# P6.net
KiCad netlist of a schematic drawn in Altium Designer
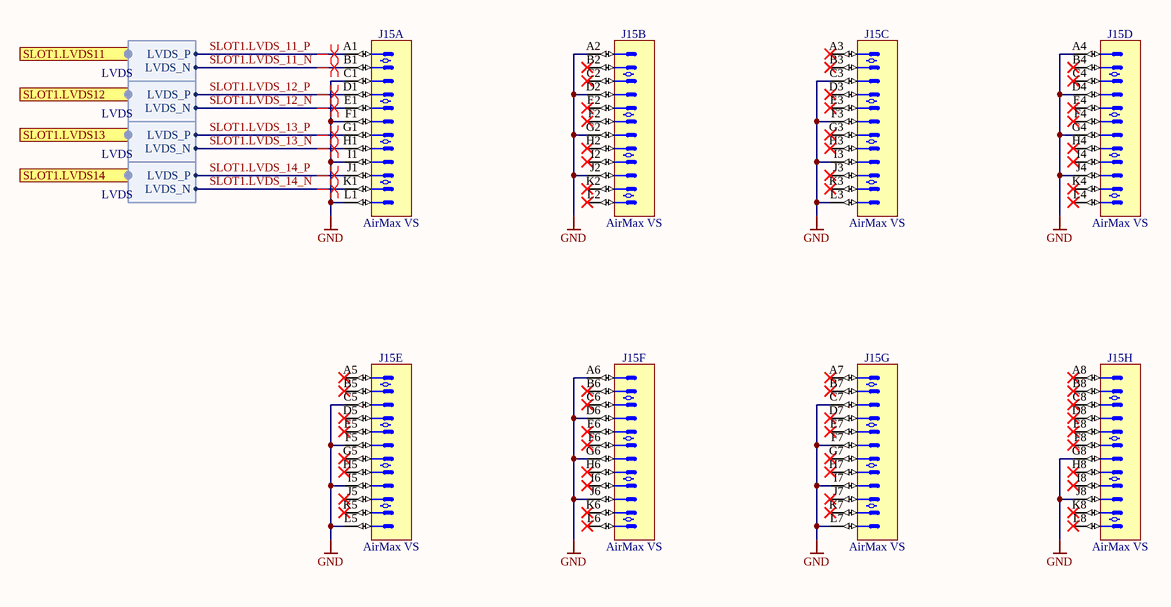
[diagram p0: P6.SchDoc]

(export (version "E")
  (design (tool "Eeschema 10.0.6"))
  (components
    (comp (ref "J15")
      (value "AirMax VS")
      (footprint "AMPHENOL_10052838-101LF")
      (description "96 Contacts Header, 8 Columns, 4 Pairs per Column")
      (fields
        (field (name "PART NUMBER") "AMPHENOL_10052838-101LF")
        (field (name "MANUFACTURER") "AMPHENOL")
        (field (name "AUTHOR") "CERN DEM MR")
      )
      (libsource (lib "Connectors") (part "AMPHENOL_10052838-101LF"))
    )
  )
  (nets
    (net (code "4") (name "/SLOT1.LVDS_11_N") (class "Default")
      (node (ref "J15") (pin "B1") (pinfunction "B1_B1") (pintype "bidirectional"))
    )
    (net (code "5") (name "/SLOT1.LVDS_11_P") (class "Default")
      (node (ref "J15") (pin "A1") (pinfunction "A1_A1") (pintype "bidirectional"))
    )
    (net (code "6") (name "/SLOT1.LVDS_12_N") (class "Default")
      (node (ref "J15") (pin "E1") (pinfunction "E1_E1") (pintype "bidirectional"))
    )
    (net (code "7") (name "/SLOT1.LVDS_12_P") (class "Default")
      (node (ref "J15") (pin "D1") (pinfunction "D1_D1") (pintype "bidirectional"))
    )
    (net (code "8") (name "/SLOT1.LVDS_13_N") (class "Default")
      (node (ref "J15") (pin "H1") (pinfunction "H1_H1") (pintype "bidirectional"))
    )
    (net (code "9") (name "/SLOT1.LVDS_13_P") (class "Default")
      (node (ref "J15") (pin "G1") (pinfunction "G1_G1") (pintype "bidirectional"))
    )
    (net (code "10") (name "/SLOT1.LVDS_14_N") (class "Default")
      (node (ref "J15") (pin "K1") (pinfunction "K1_K1") (pintype "bidirectional"))
    )
    (net (code "11") (name "/SLOT1.LVDS_14_P") (class "Default")
      (node (ref "J15") (pin "J1") (pinfunction "J1_J1") (pintype "bidirectional"))
    )
    (net (code "13") (name "GND") (class "Default")
      (node (ref "J15") (pin "A2") (pinfunction "A2_A2") (pintype "bidirectional"))
      (node (ref "J15") (pin "A4") (pinfunction "A4_A4") (pintype "bidirectional"))
      (node (ref "J15") (pin "A6") (pinfunction "A6_A6") (pintype "bidirectional"))
      (node (ref "J15") (pin "C1") (pinfunction "C1_C1") (pintype "bidirectional"))
      (node (ref "J15") (pin "C3") (pinfunction "C3_C3") (pintype "bidirectional"))
      (node (ref "J15") (pin "C5") (pinfunction "C5_C5") (pintype "bidirectional"))
      (node (ref "J15") (pin "C7") (pinfunction "C7_C7") (pintype "bidirectional"))
      (node (ref "J15") (pin "D2") (pinfunction "D2_D2") (pintype "bidirectional"))
      (node (ref "J15") (pin "D4") (pinfunction "D4_D4") (pintype "bidirectional"))
      (node (ref "J15") (pin "D6") (pinfunction "D6_D6") (pintype "bidirectional"))
      (node (ref "J15") (pin "F1") (pinfunction "F1_F1") (pintype "bidirectional"))
      (node (ref "J15") (pin "F3") (pinfunction "F3_F3") (pintype "bidirectional"))
      (node (ref "J15") (pin "F5") (pinfunction "F5_F5") (pintype "bidirectional"))
      (node (ref "J15") (pin "F7") (pinfunction "F7_F7") (pintype "bidirectional"))
      (node (ref "J15") (pin "G2") (pinfunction "G2_G2") (pintype "bidirectional"))
      (node (ref "J15") (pin "G4") (pinfunction "G4_G4") (pintype "bidirectional"))
      (node (ref "J15") (pin "G6") (pinfunction "G6_G6") (pintype "bidirectional"))
      (node (ref "J15") (pin "G8") (pinfunction "G8_G8") (pintype "bidirectional"))
      (node (ref "J15") (pin "I1") (pinfunction "I1_I1") (pintype "bidirectional"))
      (node (ref "J15") (pin "I3") (pinfunction "I3_I3") (pintype "bidirectional"))
      (node (ref "J15") (pin "I5") (pinfunction "I5_I5") (pintype "bidirectional"))
      (node (ref "J15") (pin "I7") (pinfunction "I7_I7") (pintype "bidirectional"))
      (node (ref "J15") (pin "J2") (pinfunction "J2_J2") (pintype "bidirectional"))
      (node (ref "J15") (pin "J4") (pinfunction "J4_J4") (pintype "bidirectional"))
      (node (ref "J15") (pin "J6") (pinfunction "J6_J6") (pintype "bidirectional"))
      (node (ref "J15") (pin "J8") (pinfunction "J8_J8") (pintype "bidirectional"))
      (node (ref "J15") (pin "L1") (pinfunction "L1_L1") (pintype "bidirectional"))
      (node (ref "J15") (pin "L3") (pinfunction "L3_L3") (pintype "bidirectional"))
      (node (ref "J15") (pin "L5") (pinfunction "L5_L5") (pintype "bidirectional"))
      (node (ref "J15") (pin "L7") (pinfunction "L7_L7") (pintype "bidirectional"))
    )
    (net (code "14") (name "unconnected-(J15-PadA3)") (class "Default")
      (node (ref "J15") (pin "A3") (pinfunction "A3_A3") (pintype "bidirectional+no_connect"))
    )
    (net (code "15") (name "unconnected-(J15-PadA5)") (class "Default")
      (node (ref "J15") (pin "A5") (pinfunction "A5_A5") (pintype "bidirectional+no_connect"))
    )
    (net (code "16") (name "unconnected-(J15-PadA7)") (class "Default")
      (node (ref "J15") (pin "A7") (pinfunction "A7_A7") (pintype "bidirectional+no_connect"))
    )
    (net (code "17") (name "unconnected-(J15-PadA8)") (class "Default")
      (node (ref "J15") (pin "A8") (pinfunction "A8_A8") (pintype "bidirectional+no_connect"))
    )
    (net (code "18") (name "unconnected-(J15-PadB2)") (class "Default")
      (node (ref "J15") (pin "B2") (pinfunction "B2_B2") (pintype "bidirectional+no_connect"))
    )
    (net (code "19") (name "unconnected-(J15-PadB3)") (class "Default")
      (node (ref "J15") (pin "B3") (pinfunction "B3_B3") (pintype "bidirectional+no_connect"))
    )
    (net (code "20") (name "unconnected-(J15-PadB4)") (class "Default")
      (node (ref "J15") (pin "B4") (pinfunction "B4_B4") (pintype "bidirectional+no_connect"))
    )
    (net (code "21") (name "unconnected-(J15-PadB5)") (class "Default")
      (node (ref "J15") (pin "B5") (pinfunction "B5_B5") (pintype "bidirectional+no_connect"))
    )
    (net (code "22") (name "unconnected-(J15-PadB6)") (class "Default")
      (node (ref "J15") (pin "B6") (pinfunction "B6_B6") (pintype "bidirectional+no_connect"))
    )
    (net (code "23") (name "unconnected-(J15-PadB7)") (class "Default")
      (node (ref "J15") (pin "B7") (pinfunction "B7_B7") (pintype "bidirectional+no_connect"))
    )
    (net (code "24") (name "unconnected-(J15-PadB8)") (class "Default")
      (node (ref "J15") (pin "B8") (pinfunction "B8_B8") (pintype "bidirectional+no_connect"))
    )
    (net (code "25") (name "unconnected-(J15-PadC2)") (class "Default")
      (node (ref "J15") (pin "C2") (pinfunction "C2_C2") (pintype "bidirectional+no_connect"))
    )
    (net (code "26") (name "unconnected-(J15-PadC4)") (class "Default")
      (node (ref "J15") (pin "C4") (pinfunction "C4_C4") (pintype "bidirectional+no_connect"))
    )
    (net (code "27") (name "unconnected-(J15-PadC6)") (class "Default")
      (node (ref "J15") (pin "C6") (pinfunction "C6_C6") (pintype "bidirectional+no_connect"))
    )
    (net (code "28") (name "unconnected-(J15-PadC8)") (class "Default")
      (node (ref "J15") (pin "C8") (pinfunction "C8_C8") (pintype "bidirectional+no_connect"))
    )
    (net (code "29") (name "unconnected-(J15-PadD3)") (class "Default")
      (node (ref "J15") (pin "D3") (pinfunction "D3_D3") (pintype "bidirectional+no_connect"))
    )
    (net (code "30") (name "unconnected-(J15-PadD5)") (class "Default")
      (node (ref "J15") (pin "D5") (pinfunction "D5_D5") (pintype "bidirectional+no_connect"))
    )
    (net (code "31") (name "unconnected-(J15-PadD7)") (class "Default")
      (node (ref "J15") (pin "D7") (pinfunction "D7_D7") (pintype "bidirectional+no_connect"))
    )
    (net (code "32") (name "unconnected-(J15-PadD8)") (class "Default")
      (node (ref "J15") (pin "D8") (pinfunction "D8_D8") (pintype "bidirectional+no_connect"))
    )
    (net (code "33") (name "unconnected-(J15-PadE2)") (class "Default")
      (node (ref "J15") (pin "E2") (pinfunction "E2_E2") (pintype "bidirectional+no_connect"))
    )
    (net (code "34") (name "unconnected-(J15-PadE3)") (class "Default")
      (node (ref "J15") (pin "E3") (pinfunction "E3_E3") (pintype "bidirectional+no_connect"))
    )
    (net (code "35") (name "unconnected-(J15-PadE4)") (class "Default")
      (node (ref "J15") (pin "E4") (pinfunction "E4_E4") (pintype "bidirectional+no_connect"))
    )
    (net (code "36") (name "unconnected-(J15-PadE5)") (class "Default")
      (node (ref "J15") (pin "E5") (pinfunction "E5_E5") (pintype "bidirectional+no_connect"))
    )
    (net (code "37") (name "unconnected-(J15-PadE6)") (class "Default")
      (node (ref "J15") (pin "E6") (pinfunction "E6_E6") (pintype "bidirectional+no_connect"))
    )
    (net (code "38") (name "unconnected-(J15-PadE7)") (class "Default")
      (node (ref "J15") (pin "E7") (pinfunction "E7_E7") (pintype "bidirectional+no_connect"))
    )
    (net (code "39") (name "unconnected-(J15-PadE8)") (class "Default")
      (node (ref "J15") (pin "E8") (pinfunction "E8_E8") (pintype "bidirectional+no_connect"))
    )
    (net (code "40") (name "unconnected-(J15-PadF2)") (class "Default")
      (node (ref "J15") (pin "F2") (pinfunction "F2_F2") (pintype "bidirectional+no_connect"))
    )
    (net (code "41") (name "unconnected-(J15-PadF4)") (class "Default")
      (node (ref "J15") (pin "F4") (pinfunction "F4_F4") (pintype "bidirectional+no_connect"))
    )
    (net (code "42") (name "unconnected-(J15-PadF6)") (class "Default")
      (node (ref "J15") (pin "F6") (pinfunction "F6_F6") (pintype "bidirectional+no_connect"))
    )
    (net (code "43") (name "unconnected-(J15-PadF8)") (class "Default")
      (node (ref "J15") (pin "F8") (pinfunction "F8_F8") (pintype "bidirectional+no_connect"))
    )
    (net (code "44") (name "unconnected-(J15-PadG3)") (class "Default")
      (node (ref "J15") (pin "G3") (pinfunction "G3_G3") (pintype "bidirectional+no_connect"))
    )
    (net (code "45") (name "unconnected-(J15-PadG5)") (class "Default")
      (node (ref "J15") (pin "G5") (pinfunction "G5_G5") (pintype "bidirectional+no_connect"))
    )
    (net (code "46") (name "unconnected-(J15-PadG7)") (class "Default")
      (node (ref "J15") (pin "G7") (pinfunction "G7_G7") (pintype "bidirectional+no_connect"))
    )
    (net (code "47") (name "unconnected-(J15-PadH2)") (class "Default")
      (node (ref "J15") (pin "H2") (pinfunction "H2_H2") (pintype "bidirectional+no_connect"))
    )
    (net (code "48") (name "unconnected-(J15-PadH3)") (class "Default")
      (node (ref "J15") (pin "H3") (pinfunction "H3_H3") (pintype "bidirectional+no_connect"))
    )
    (net (code "49") (name "unconnected-(J15-PadH4)") (class "Default")
      (node (ref "J15") (pin "H4") (pinfunction "H4_H4") (pintype "bidirectional+no_connect"))
    )
    (net (code "50") (name "unconnected-(J15-PadH5)") (class "Default")
      (node (ref "J15") (pin "H5") (pinfunction "H5_H5") (pintype "bidirectional+no_connect"))
    )
    (net (code "51") (name "unconnected-(J15-PadH6)") (class "Default")
      (node (ref "J15") (pin "H6") (pinfunction "H6_H6") (pintype "bidirectional+no_connect"))
    )
    (net (code "52") (name "unconnected-(J15-PadH7)") (class "Default")
      (node (ref "J15") (pin "H7") (pinfunction "H7_H7") (pintype "bidirectional+no_connect"))
    )
    (net (code "53") (name "unconnected-(J15-PadH8)") (class "Default")
      (node (ref "J15") (pin "H8") (pinfunction "H8_H8") (pintype "bidirectional+no_connect"))
    )
    (net (code "54") (name "unconnected-(J15-PadI2)") (class "Default")
      (node (ref "J15") (pin "I2") (pinfunction "I2_I2") (pintype "bidirectional+no_connect"))
    )
    (net (code "55") (name "unconnected-(J15-PadI4)") (class "Default")
      (node (ref "J15") (pin "I4") (pinfunction "I4_I4") (pintype "bidirectional+no_connect"))
    )
    (net (code "56") (name "unconnected-(J15-PadI6)") (class "Default")
      (node (ref "J15") (pin "I6") (pinfunction "I6_I6") (pintype "bidirectional+no_connect"))
    )
    (net (code "57") (name "unconnected-(J15-PadI8)") (class "Default")
      (node (ref "J15") (pin "I8") (pinfunction "I8_I8") (pintype "bidirectional+no_connect"))
    )
    (net (code "58") (name "unconnected-(J15-PadJ3)") (class "Default")
      (node (ref "J15") (pin "J3") (pinfunction "J3_J3") (pintype "bidirectional+no_connect"))
    )
    (net (code "59") (name "unconnected-(J15-PadJ5)") (class "Default")
      (node (ref "J15") (pin "J5") (pinfunction "J5_J5") (pintype "bidirectional+no_connect"))
    )
    (net (code "60") (name "unconnected-(J15-PadJ7)") (class "Default")
      (node (ref "J15") (pin "J7") (pinfunction "J7_J7") (pintype "bidirectional+no_connect"))
    )
    (net (code "61") (name "unconnected-(J15-PadK2)") (class "Default")
      (node (ref "J15") (pin "K2") (pinfunction "K2_K2") (pintype "bidirectional+no_connect"))
    )
    (net (code "62") (name "unconnected-(J15-PadK3)") (class "Default")
      (node (ref "J15") (pin "K3") (pinfunction "K3_K3") (pintype "bidirectional+no_connect"))
    )
    (net (code "63") (name "unconnected-(J15-PadK4)") (class "Default")
      (node (ref "J15") (pin "K4") (pinfunction "K4_K4") (pintype "bidirectional+no_connect"))
    )
    (net (code "64") (name "unconnected-(J15-PadK5)") (class "Default")
      (node (ref "J15") (pin "K5") (pinfunction "K5_K5") (pintype "bidirectional+no_connect"))
    )
    (net (code "65") (name "unconnected-(J15-PadK6)") (class "Default")
      (node (ref "J15") (pin "K6") (pinfunction "K6_K6") (pintype "bidirectional+no_connect"))
    )
    (net (code "66") (name "unconnected-(J15-PadK7)") (class "Default")
      (node (ref "J15") (pin "K7") (pinfunction "K7_K7") (pintype "bidirectional+no_connect"))
    )
    (net (code "67") (name "unconnected-(J15-PadK8)") (class "Default")
      (node (ref "J15") (pin "K8") (pinfunction "K8_K8") (pintype "bidirectional+no_connect"))
    )
    (net (code "68") (name "unconnected-(J15-PadL2)") (class "Default")
      (node (ref "J15") (pin "L2") (pinfunction "L2_L2") (pintype "bidirectional+no_connect"))
    )
    (net (code "69") (name "unconnected-(J15-PadL4)") (class "Default")
      (node (ref "J15") (pin "L4") (pinfunction "L4_L4") (pintype "bidirectional+no_connect"))
    )
    (net (code "70") (name "unconnected-(J15-PadL6)") (class "Default")
      (node (ref "J15") (pin "L6") (pinfunction "L6_L6") (pintype "bidirectional+no_connect"))
    )
    (net (code "71") (name "unconnected-(J15-PadL8)") (class "Default")
      (node (ref "J15") (pin "L8") (pinfunction "L8_L8") (pintype "bidirectional+no_connect"))
    )
  )
)
